# Sensors_Actuators.net
KiCad netlist of a schematic drawn in Altium Designer
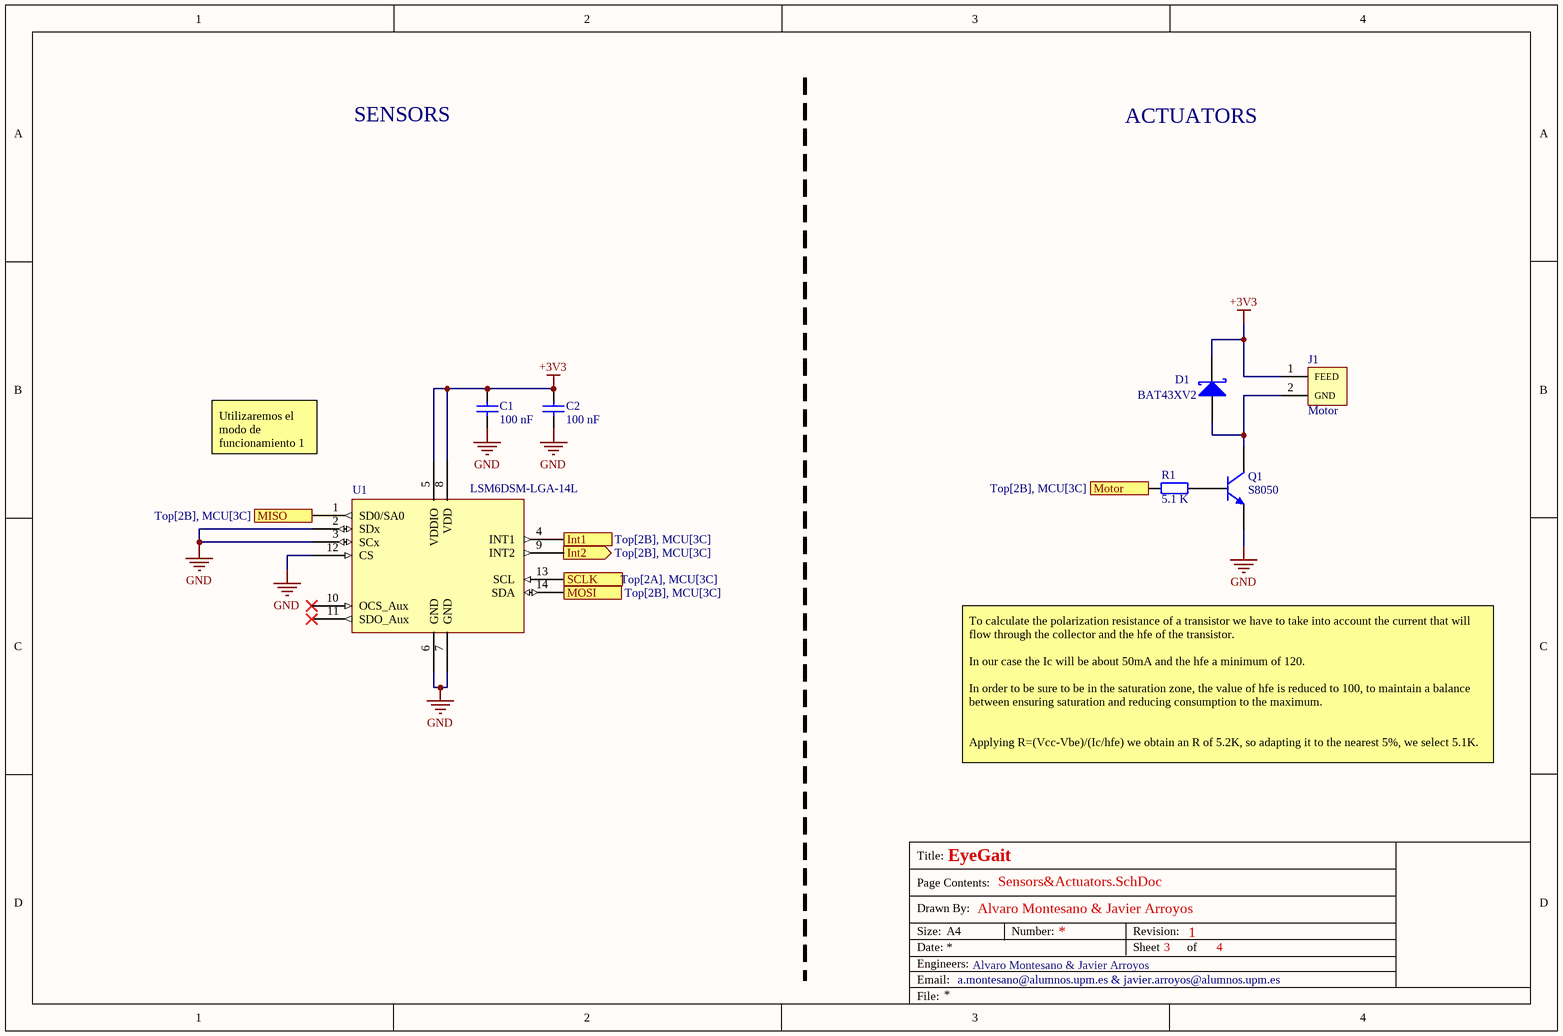
[diagram p0: Sensors&Actuators.SchDoc]

(export (version "E")
  (design (tool "Eeschema 10.0.6"))
  (components
    (comp (ref "C1")
      (value "100 nF")
      (footprint "C0402")
      (description "Capacitor")
      (libsource (lib "DEOP2324") (part "C"))
    )
    (comp (ref "C2")
      (value "100 nF")
      (footprint "C0402")
      (description "Capacitor")
      (libsource (lib "DEOP2324") (part "C"))
    )
    (comp (ref "D1")
      (value "BAT43XV2")
      (footprint "SOD_523")
      (description "Schottky Diode")
      (libsource (lib "DEOP2324") (part "D Schottky"))
    )
    (comp (ref "J1")
      (value "Motor")
      (footprint "Hand solder wire polarity")
      (libsource (lib "DEOP2324") (part "Motor"))
    )
    (comp (ref "Q1")
      (value "S8050")
      (footprint "SOT23")
      (description "NPN Bipolar Transistor")
      (libsource (lib "DEOP2324") (part "NPN"))
    )
    (comp (ref "R1")
      (value "5.1 K")
      (footprint "R0402")
      (description "Resistor")
      (libsource (lib "DEOP2324") (part "R"))
    )
    (comp (ref "U1")
      (value "LSM6DSM-LGA-14L")
      (footprint "LSM6DSM-LGA-14L-v2")
      (description "6-axis IMU, Accel&Gyro")
      (libsource (lib "DEOP2324") (part "LSM6DSM-LGA-14L"))
    )
  )
  (nets
    (net (code "1") (name "+3V3") (class "Default")
      (node (ref "C1") (pin "1") (pinfunction "1_1") (pintype "passive"))
      (node (ref "C2") (pin "1") (pinfunction "1_1") (pintype "passive"))
      (node (ref "D1") (pin "2") (pinfunction "K_2") (pintype "passive"))
      (node (ref "J1") (pin "1") (pinfunction "FEED_1") (pintype "power_in"))
      (node (ref "U1") (pin "5") (pinfunction "VDDIO_5") (pintype "power_in"))
      (node (ref "U1") (pin "8") (pinfunction "VDD_8") (pintype "power_in"))
    )
    (net (code "2") (name "/Int1") (class "Default")
      (node (ref "U1") (pin "4") (pinfunction "INT1_4") (pintype "output"))
    )
    (net (code "3") (name "/Int2") (class "Default")
      (node (ref "U1") (pin "9") (pinfunction "INT2_9") (pintype "output"))
    )
    (net (code "4") (name "/MISO") (class "Default")
      (node (ref "U1") (pin "1") (pinfunction "SD0/SA0_1") (pintype "output"))
    )
    (net (code "5") (name "/MOSI") (class "Default")
      (node (ref "U1") (pin "14") (pinfunction "SDA_14") (pintype "bidirectional"))
    )
    (net (code "6") (name "/Motor") (class "Default")
      (node (ref "R1") (pin "1") (pinfunction "1_1") (pintype "passive"))
    )
    (net (code "7") (name "/SCLK") (class "Default")
      (node (ref "U1") (pin "13") (pinfunction "SCL_13") (pintype "input"))
    )
    (net (code "8") (name "GND") (class "Default")
      (node (ref "C1") (pin "2") (pinfunction "2_2") (pintype "passive"))
      (node (ref "C2") (pin "2") (pinfunction "2_2") (pintype "passive"))
      (node (ref "Q1") (pin "2") (pinfunction "E_2") (pintype "passive"))
      (node (ref "U1") (pin "12") (pinfunction "CS_12") (pintype "input"))
      (node (ref "U1") (pin "2") (pinfunction "SDx_2") (pintype "bidirectional"))
      (node (ref "U1") (pin "3") (pinfunction "SCx_3") (pintype "bidirectional"))
      (node (ref "U1") (pin "6") (pinfunction "GND_6") (pintype "power_in"))
      (node (ref "U1") (pin "7") (pinfunction "GND_7") (pintype "power_in"))
    )
    (net (code "9") (name "Net-(D1-A)") (class "Default")
      (node (ref "D1") (pin "1") (pinfunction "A_1") (pintype "passive"))
      (node (ref "J1") (pin "2") (pinfunction "GND_2") (pintype "power_in"))
      (node (ref "Q1") (pin "3") (pinfunction "C_3") (pintype "passive"))
    )
    (net (code "10") (name "Net-(Q1-B)") (class "Default")
      (node (ref "Q1") (pin "1") (pinfunction "B_1") (pintype "passive"))
      (node (ref "R1") (pin "2") (pinfunction "2_2") (pintype "passive"))
    )
    (net (code "11") (name "unconnected-(U1-OCS_Aux-Pad10)") (class "Default")
      (node (ref "U1") (pin "10") (pinfunction "OCS_Aux_10") (pintype "input+no_connect"))
    )
    (net (code "12") (name "unconnected-(U1-SDO_Aux-Pad11)") (class "Default")
      (node (ref "U1") (pin "11") (pinfunction "SDO_Aux_11") (pintype "output+no_connect"))
    )
  )
)
